# SWDM-21DD8_LV_XX_V1.net
KiCad netlist of a schematic drawn in Altium Designer
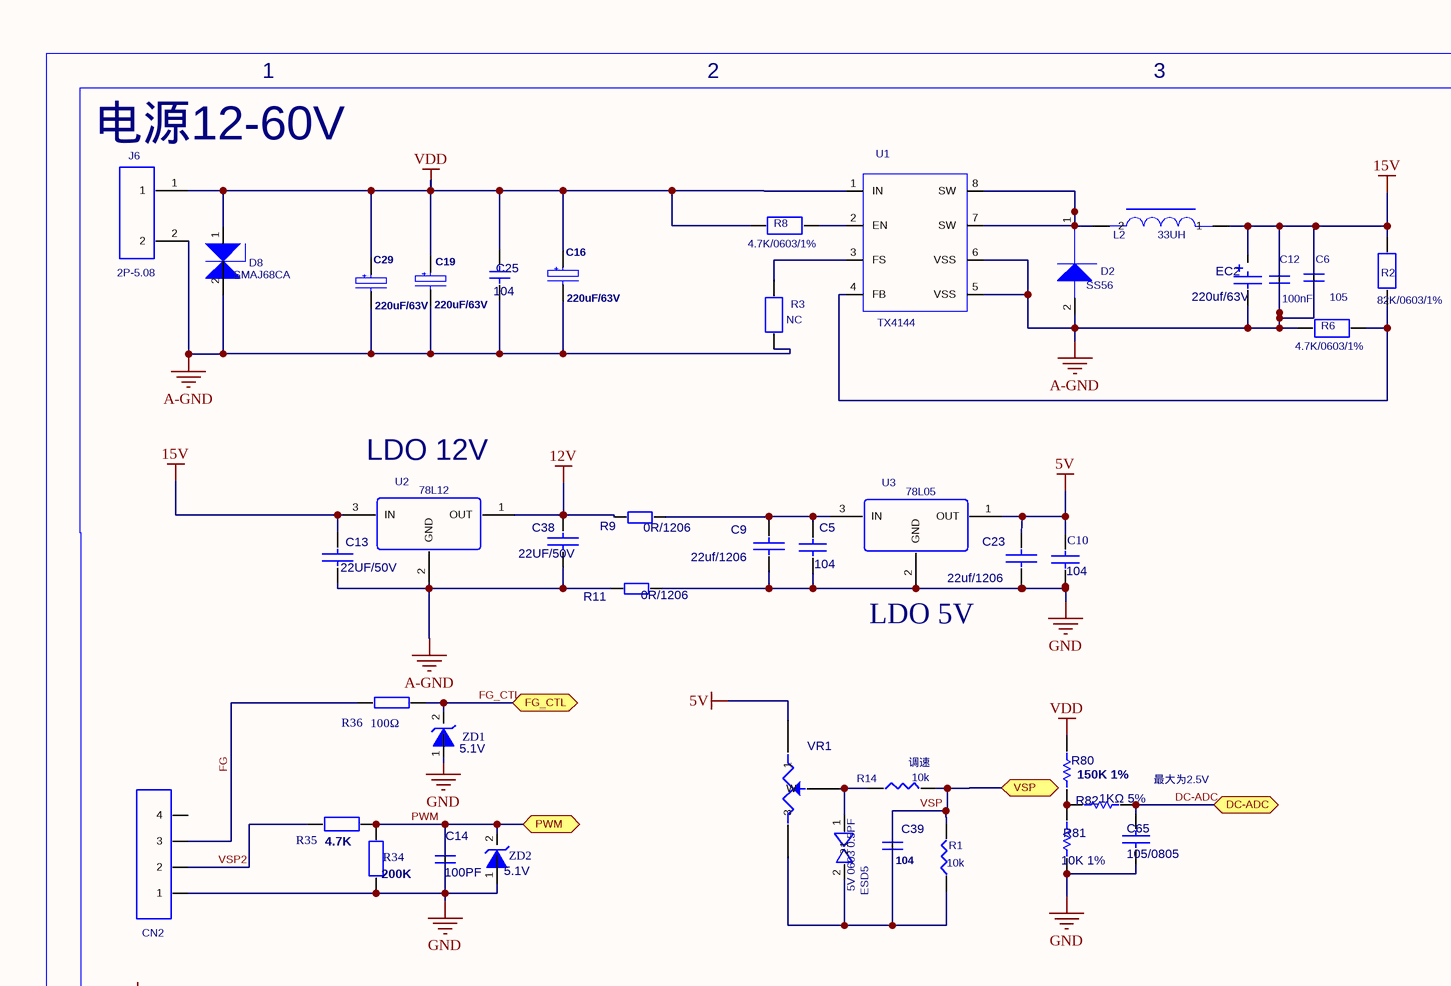
[diagram p0: SWDM-21DD8_LV_XX_V1.SchDoc, top left]
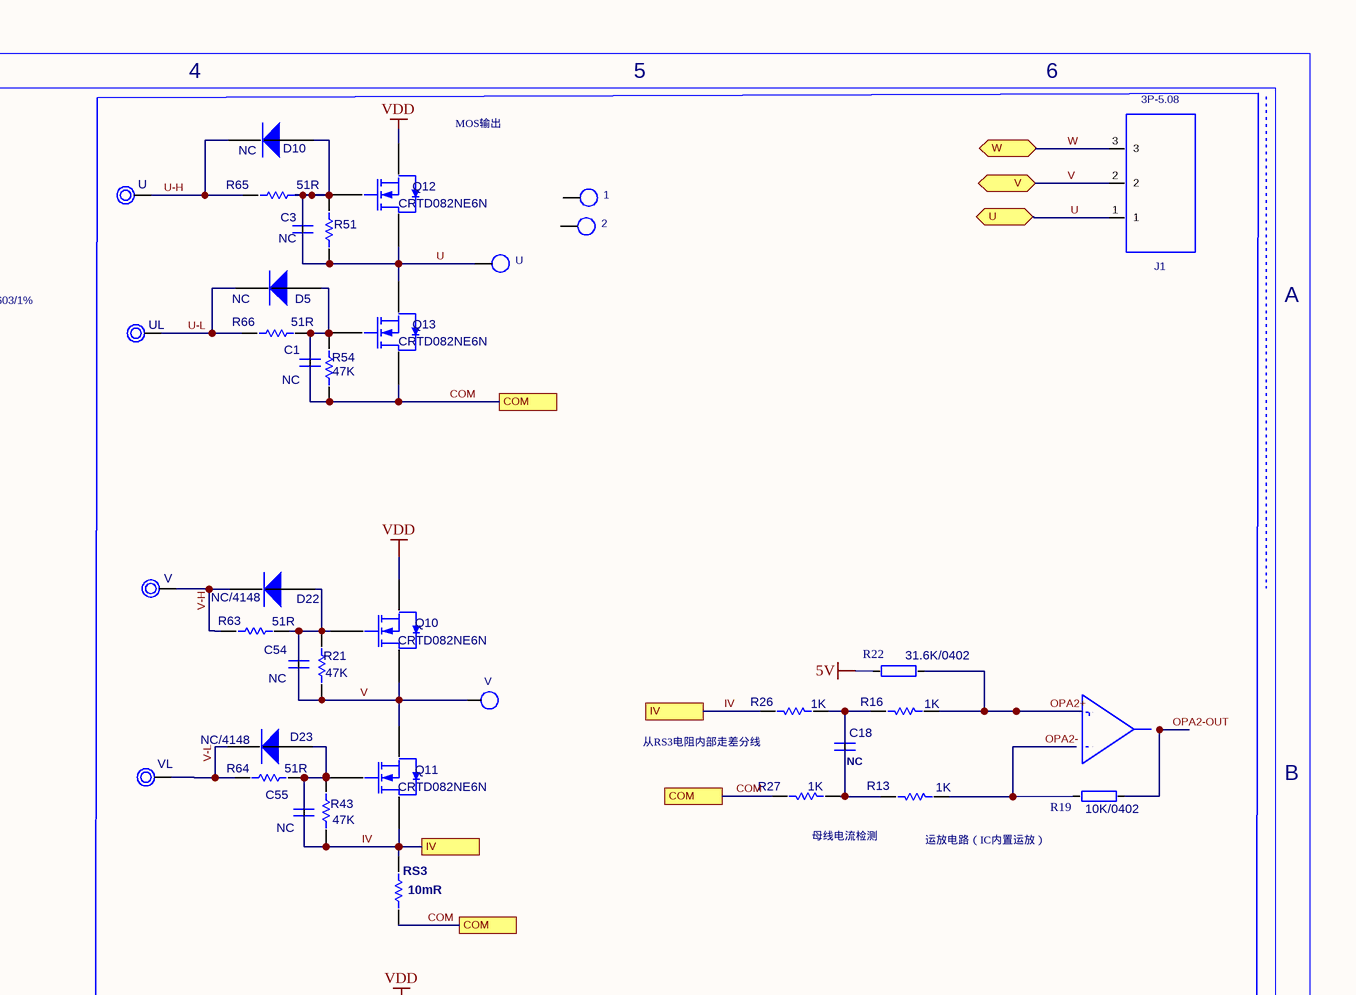
[diagram p1: SWDM-21DD8_LV_XX_V1.SchDoc, top right]
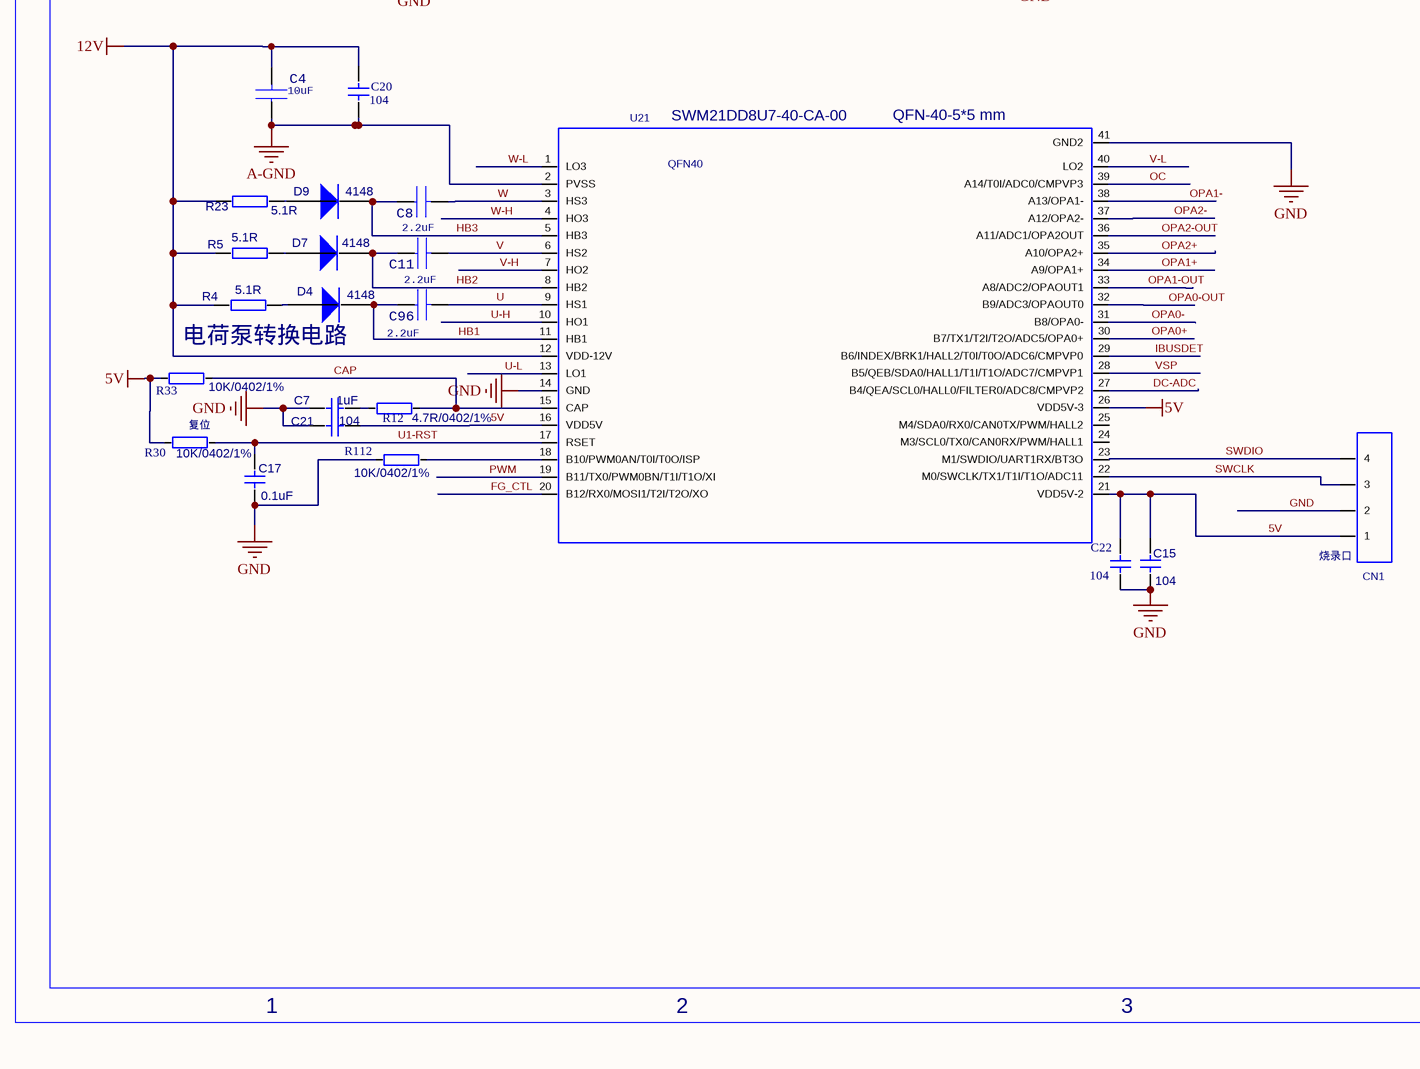
[diagram p2: SWDM-21DD8_LV_XX_V1.SchDoc, bottom left]
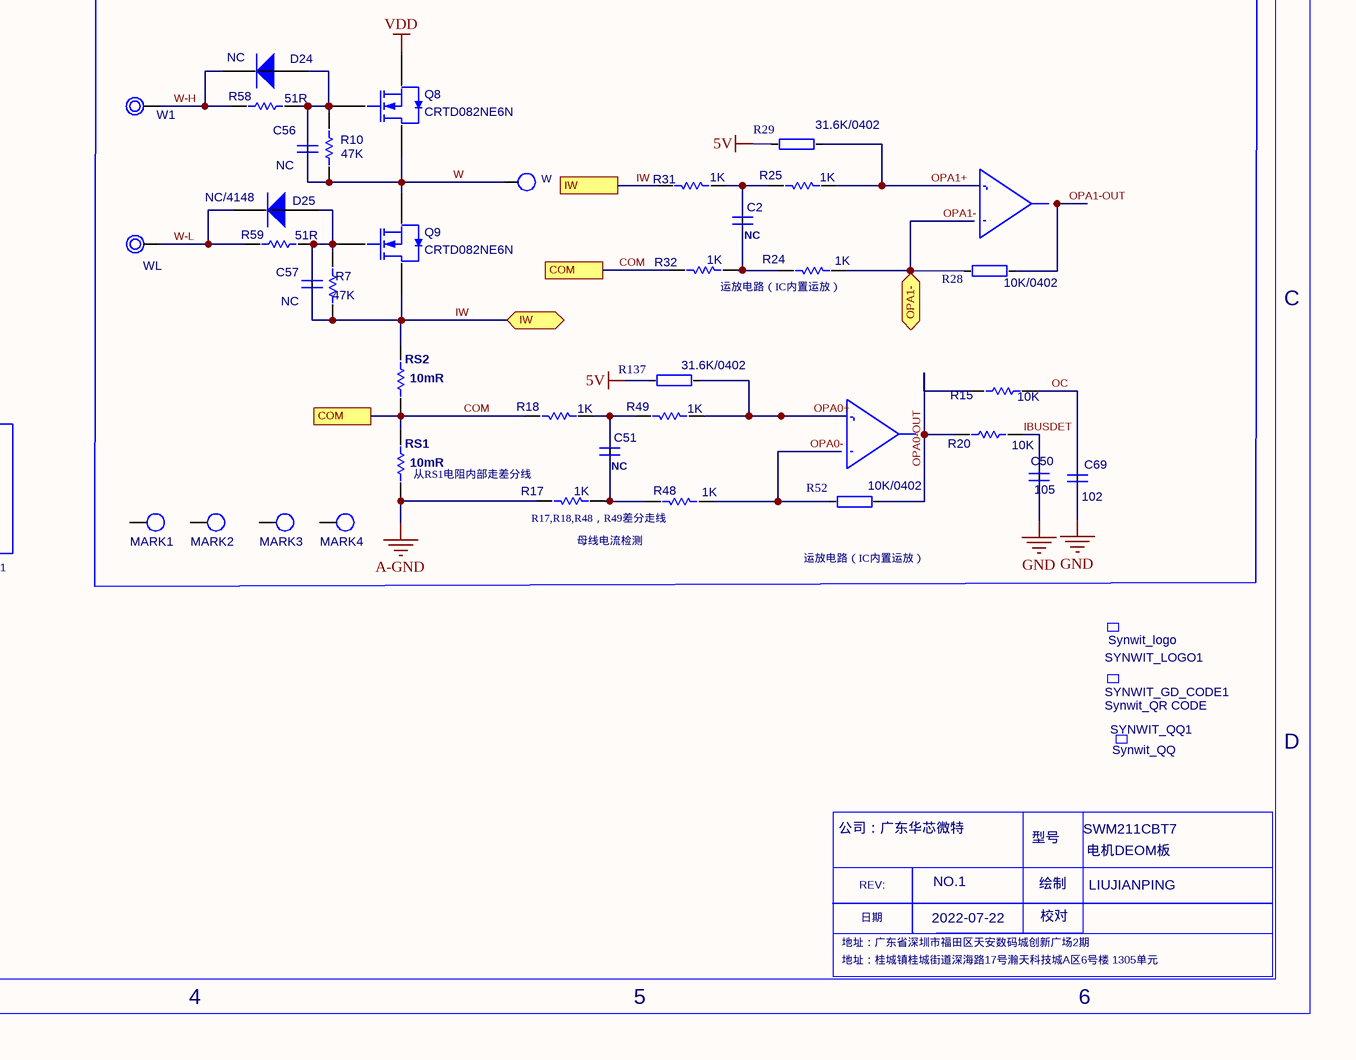
[diagram p3: SWDM-21DD8_LV_XX_V1.SchDoc, bottom right]

(export (version "E")
  (design (tool "Eeschema 10.0.6"))
  (components
    (comp (ref "C1")
      (value "NC")
      (footprint "C0603")
      (description "贴片瓷片电容")
      (libsource (lib "*") (part "C0603"))
    )
    (comp (ref "C2")
      (value "NC")
      (footprint "C0603")
      (fields (field (name "Comment") "C0603"))
      (libsource (lib "*") (part "C0603"))
    )
    (comp (ref "C3")
      (value "NC")
      (footprint "C0603")
      (description "贴片瓷片电容")
      (libsource (lib "*") (part "C0603"))
    )
    (comp (ref "C4")
      (value "10uF")
      (footprint "C0805")
      (description "SMT Resistor 5% UniOhm(厚声)")
      (fields (field (name "Comment") "22uf/25v"))
      (libsource (lib "*") (part "C0805"))
    )
    (comp (ref "C5")
      (value "104")
      (footprint "C0603")
      (description "贴片瓷片电容")
      (libsource (lib "*") (part "CAP_2"))
    )
    (comp (ref "C6")
      (value "105")
      (footprint "C0603")
      (fields (field (name "Comment") "C0603"))
      (libsource (lib "*") (part "C0603"))
    )
    (comp (ref "C7") (value "1uF") (footprint "C0603") (libsource (lib "*") (part "CAP_S")))
    (comp (ref "C8")
      (value "2.2uF")
      (footprint "C0805")
      (fields (field (name "Comment") "C0805"))
      (libsource (lib "*") (part "C0805"))
    )
    (comp (ref "C9")
      (value "22uf/1206")
      (footprint "C1206")
      (description "Capacitor")
      (libsource (lib "*") (part "C1206"))
    )
    (comp (ref "C10")
      (value "104")
      (footprint "C0603")
      (description "贴片瓷片电容")
      (libsource (lib "*") (part "CAP_2"))
    )
    (comp (ref "C11")
      (value "2.2uF")
      (footprint "C0805")
      (fields (field (name "Comment") "C0805"))
      (libsource (lib "*") (part "C0805"))
    )
    (comp (ref "C12")
      (value "100nF")
      (footprint "C0603")
      (fields (field (name "Comment") "C0603"))
      (libsource (lib "*") (part "C0603"))
    )
    (comp (ref "C13")
      (value "22UF/50V")
      (footprint "C1206")
      (description "电解电容")
      (libsource (lib "*") (part "C1206"))
    )
    (comp (ref "C14")
      (value "100PF")
      (footprint "C0603")
      (description "Capacitor")
      (libsource (lib "*") (part "C0603"))
    )
    (comp (ref "C15") (value "104") (footprint "C0603") (libsource (lib "*") (part "CAP_S")))
    (comp (ref "C16")
      (value "220uF/63V")
      (footprint "CAP_10X12")
      (fields
        (field (name "VOLTAGE") "16V")
        (field (name "TOLERANCE") "20%")
        (field (name "Comment") "CAP_10X12")
      )
      (libsource (lib "*") (part "CAP_10X12"))
    )
    (comp (ref "C17") (value "0.1uF") (footprint "C0603") (libsource (lib "*") (part "CAP_S")))
    (comp (ref "C18")
      (value "NC")
      (footprint "C0603")
      (fields (field (name "Comment") "C0603"))
      (libsource (lib "*") (part "C0603"))
    )
    (comp (ref "C19")
      (value "220uF/63V")
      (footprint "CAP_10X12")
      (fields
        (field (name "VOLTAGE") "16V")
        (field (name "TOLERANCE") "20%")
        (field (name "Comment") "CAP_10X12")
      )
      (libsource (lib "*") (part "CAP_10X12"))
    )
    (comp (ref "C20") (value "104") (footprint "C0603") (libsource (lib "*") (part "CAP_S")))
    (comp (ref "C21") (value "104") (footprint "C0603") (libsource (lib "*") (part "CAP_S")))
    (comp (ref "C22") (value "104") (footprint "C0603") (libsource (lib "*") (part "CAP_S")))
    (comp (ref "C23")
      (value "22uf/1206")
      (footprint "C1206")
      (description "Capacitor")
      (libsource (lib "*") (part "C1206"))
    )
    (comp (ref "C25") (value "104") (footprint "C0603") (libsource (lib "*") (part "CAP_S")))
    (comp (ref "C29")
      (value "220uF/63V")
      (footprint "CAP_10X12")
      (fields
        (field (name "VOLTAGE") "16V")
        (field (name "TOLERANCE") "20%")
        (field (name "Comment") "CAP_10X12")
      )
      (libsource (lib "*") (part "CAP_10X12"))
    )
    (comp (ref "C38")
      (value "22UF/50V")
      (footprint "C1206")
      (description "电解电容")
      (libsource (lib "*") (part "C1206"))
    )
    (comp (ref "C39")
      (value "104")
      (footprint "C0603")
      (fields (field (name "Comment") "C0603"))
      (libsource (lib "") (part "C0603_1"))
    )
    (comp (ref "C50")
      (value "105")
      (footprint "C0603")
      (description "贴片瓷片电容")
      (libsource (lib "*") (part "C0603"))
    )
    (comp (ref "C51")
      (value "NC")
      (footprint "C0603")
      (fields (field (name "Comment") "C0603"))
      (libsource (lib "*") (part "C0603"))
    )
    (comp (ref "C54")
      (value "NC")
      (footprint "C0603")
      (description "贴片瓷片电容")
      (libsource (lib "*") (part "C0603"))
    )
    (comp (ref "C55")
      (value "NC")
      (footprint "C0603")
      (description "贴片瓷片电容")
      (libsource (lib "*") (part "C0603"))
    )
    (comp (ref "C56")
      (value "NC")
      (footprint "C0603")
      (description "贴片瓷片电容")
      (libsource (lib "") (part "C0603_1"))
    )
    (comp (ref "C57")
      (value "NC")
      (footprint "C0603")
      (description "贴片瓷片电容")
      (libsource (lib "*") (part "C0603"))
    )
    (comp (ref "C65")
      (value "105/0805")
      (footprint "C0603")
      (description "Capacitor")
      (libsource (lib "*") (part "CAP"))
    )
    (comp (ref "C69")
      (value "102")
      (footprint "C0603")
      (description "贴片瓷片电容")
      (libsource (lib "") (part "C0603_1"))
    )
    (comp (ref "C96")
      (value "2.2uF")
      (footprint "C0805")
      (fields (field (name "Comment") "C0805"))
      (libsource (lib "*") (part "C0805"))
    )
    (comp (ref "CN1")
      (value "SWD1")
      (footprint "4P-2.54-8")
      (description "接插件  DS-5.1CN4  DS-2.54CWB-4")
      (libsource (lib "*") (part "4P-2.54-8"))
    )
    (comp (ref "CN2")
      (value "SWD1")
      (footprint "4P-2.54-8")
      (description "接插件  DS-5.1CN4  DS-2.54CWB-4")
      (libsource (lib "*") (part "4P-2.54-8"))
    )
    (comp (ref "D2")
      (value "SS56")
      (footprint "SMA")
      (fields (field (name "PART_NUMBER") "DIO-4148-01") (field (name "Comment") "DIODE_2"))
      (libsource (lib "*") (part "DIODE_2"))
    )
    (comp (ref "D4")
      (value "4148")
      (footprint "SOD-123/3")
      (description "Default Diode")
      (libsource (lib "*") (part "DIODE"))
    )
    (comp (ref "D5")
      (value "NC")
      (footprint "SOD-323")
      (description "Default Diode")
      (libsource (lib "*") (part "DIODE"))
    )
    (comp (ref "D7")
      (value "4148")
      (footprint "SOD-123/3")
      (description "Default Diode")
      (libsource (lib "*") (part "DIODE"))
    )
    (comp (ref "D8")
      (value "SMAJ68CA")
      (footprint "Y_SMA-TVS")
      (fields (field (name "PART_NUMBER") "DIO-4148-01") (field (name "Comment") "DIODE_4"))
      (libsource (lib "*") (part "DIODE_4"))
    )
    (comp (ref "D9")
      (value "4148")
      (footprint "SOD-123/3")
      (description "Default Diode")
      (libsource (lib "*") (part "DIODE"))
    )
    (comp (ref "D10")
      (value "NC")
      (footprint "SOD-323")
      (description "Default Diode")
      (libsource (lib "*") (part "DIODE"))
    )
    (comp (ref "D22")
      (value "NC/4148")
      (footprint "SOD-323")
      (description "Default Diode")
      (libsource (lib "*") (part "DIODE"))
    )
    (comp (ref "D23")
      (value "NC/4148")
      (footprint "SOD-323")
      (description "Default Diode")
      (libsource (lib "*") (part "DIODE"))
    )
    (comp (ref "D24")
      (value "NC")
      (footprint "SOD-323")
      (description "Default Diode")
      (libsource (lib "*") (part "DIODE"))
    )
    (comp (ref "D25")
      (value "NC/4148")
      (footprint "SOD-323")
      (description "Default Diode")
      (libsource (lib "*") (part "DIODE"))
    )
    (comp (ref "EC2")
      (value "220uf/63V")
      (footprint "C-DD6X9")
      (description "Polarized Capacitor (Axial)")
      (libsource (lib "*") (part "CAP_POL2"))
    )
    (comp (ref "ESD5")
      (value "5V 0603 0.5PF")
      (footprint "ESD0603")
      (fields (field (name "Comment") "ESD0603"))
      (libsource (lib "*") (part "ESD0603"))
    )
    (comp (ref "J1") (value "3P-5.08") (footprint "3P-5.08") (libsource (lib "*") (part "3P-5.08")))
    (comp (ref "J6") (value "2P-5.08") (footprint "2P-5.08") (libsource (lib "*") (part "2P-5.08")))
    (comp (ref "L2")
      (value "33UH")
      (footprint "L-8050")
      (fields (field (name "Comment") "L-8050"))
      (libsource (lib "*") (part "L-8050"))
    )
    (comp (ref "MARK1") (value "TEST POINT") (footprint "TP60") (libsource (lib "*") (part "TEST_POINT")))
    (comp (ref "MARK2") (value "TEST POINT") (footprint "TP60") (libsource (lib "*") (part "TEST_POINT")))
    (comp (ref "MARK3") (value "TEST POINT") (footprint "TP60") (libsource (lib "*") (part "TEST_POINT")))
    (comp (ref "MARK4") (value "TEST POINT") (footprint "TP60") (libsource (lib "*") (part "TEST_POINT")))
    (comp (ref "Q8")
      (value "CRTD082NE6N")
      (footprint "TO-252-2-180")
      (description "MOS(场效应管)")
      (libsource (lib "*") (part "AO3400A_NZKDZ_X0YV1T_SOT-23"))
    )
    (comp (ref "Q9")
      (value "CRTD082NE6N")
      (footprint "TO-252-2-180")
      (description "MOS(场效应管)")
      (libsource (lib "*") (part "AO3400A_NZKDZ_X0YV1T_SOT-23"))
    )
    (comp (ref "Q10")
      (value "CRTD082NE6N")
      (footprint "TO-252-2-180")
      (description "MOS(场效应管)")
      (libsource (lib "*") (part "AO3400A_NZKDZ_X0YV1T_SOT-23"))
    )
    (comp (ref "Q11")
      (value "CRTD082NE6N")
      (footprint "TO-252-2-180")
      (description "MOS(场效应管)")
      (libsource (lib "*") (part "AO3400A_NZKDZ_X0YV1T_SOT-23"))
    )
    (comp (ref "Q12")
      (value "CRTD082NE6N")
      (footprint "TO-252-2-180")
      (description "MOS(场效应管)")
      (libsource (lib "*") (part "AO3400A_NZKDZ_X0YV1T_SOT-23"))
    )
    (comp (ref "Q13")
      (value "CRTD082NE6N")
      (footprint "TO-252-2-180")
      (description "MOS(场效应管)")
      (libsource (lib "*") (part "AO3400A_NZKDZ_X0YV1T_SOT-23"))
    )
    (comp (ref "R1")
      (value "10K")
      (footprint "R0603")
      (fields (field (name "COMMENT_1") "10k"))
      (libsource (lib "") (part "10K_2_1"))
    )
    (comp (ref "R2") (value "82K/0603/1%") (footprint "R0603") (libsource (lib "*") (part "R0603")))
    (comp (ref "R3") (value "NC") (footprint "R0603") (libsource (lib "*") (part "R0603")))
    (comp (ref "R4") (value "5.1R") (footprint "R1206") (libsource (lib "*") (part "RES_T")))
    (comp (ref "R5") (value "5.1R") (footprint "R1206") (libsource (lib "*") (part "RES_T")))
    (comp (ref "R6") (value "4.7K/0603/1%") (footprint "R0603") (libsource (lib "*") (part "R0603")))
    (comp (ref "R7")
      (value "47K")
      (footprint "R0603")
      (description "Semiconductor Resistor")
      (libsource (lib "*") (part "RES_SEMI"))
    )
    (comp (ref "R8") (value "4.7K/0603/1%") (footprint "R0603") (libsource (lib "*") (part "R0603")))
    (comp (ref "R9")
      (value "0R/1206")
      (footprint "1206R")
      (description "贴片 电阻器")
      (libsource (lib "") (part "R1206_1"))
    )
    (comp (ref "R10")
      (value "47K")
      (footprint "R0603")
      (description "Semiconductor Resistor")
      (libsource (lib "*") (part "RES_SEMI"))
    )
    (comp (ref "R11")
      (value "0R/1206")
      (footprint "1206R")
      (description "贴片 电阻器")
      (libsource (lib "*") (part "R1206"))
    )
    (comp (ref "R12")
      (value "4.7R/0402/1%")
      (footprint "R0603")
      (description "贴片电阻")
      (libsource (lib "*") (part "R0402"))
    )
    (comp (ref "R13")
      (value "1K")
      (footprint "R0603")
      (description "Semiconductor Resistor")
      (libsource (lib "*") (part "RES_SEMI"))
    )
    (comp (ref "R14")
      (value "10K")
      (footprint "R0603")
      (fields (field (name "COMMENT_1") "10k"))
      (libsource (lib "*") (part "10K_2"))
    )
    (comp (ref "R15")
      (value "10K")
      (footprint "R0603")
      (description "Semiconductor Resistor")
      (libsource (lib "*") (part "RES_SEMI"))
    )
    (comp (ref "R16")
      (value "1K")
      (footprint "R0603")
      (description "Semiconductor Resistor")
      (libsource (lib "*") (part "RES_SEMI"))
    )
    (comp (ref "R17")
      (value "1K")
      (footprint "R0603")
      (description "Semiconductor Resistor")
      (libsource (lib "*") (part "RES_SEMI"))
    )
    (comp (ref "R18")
      (value "1K")
      (footprint "R0603")
      (description "Semiconductor Resistor")
      (libsource (lib "*") (part "RES_SEMI"))
    )
    (comp (ref "R19")
      (value "10K/0402")
      (footprint "R0603")
      (description "贴片电阻")
      (libsource (lib "*") (part "R0402"))
    )
    (comp (ref "R20")
      (value "10K")
      (footprint "R0603")
      (description "Semiconductor Resistor")
      (libsource (lib "*") (part "RES_SEMI"))
    )
    (comp (ref "R21")
      (value "47K")
      (footprint "R0603")
      (description "Semiconductor Resistor")
      (libsource (lib "*") (part "RES_SEMI"))
    )
    (comp (ref "R22")
      (value "31.6K/0402")
      (footprint "R0603")
      (description "贴片电阻")
      (libsource (lib "*") (part "R0402"))
    )
    (comp (ref "R23") (value "5.1R") (footprint "R1206") (libsource (lib "*") (part "RES_T")))
    (comp (ref "R24")
      (value "1K")
      (footprint "R0603")
      (description "Semiconductor Resistor")
      (libsource (lib "*") (part "RES_SEMI"))
    )
    (comp (ref "R25")
      (value "1K")
      (footprint "R0603")
      (description "Semiconductor Resistor")
      (libsource (lib "*") (part "RES_SEMI"))
    )
    (comp (ref "R26")
      (value "1K")
      (footprint "R0603")
      (description "Semiconductor Resistor")
      (libsource (lib "*") (part "RES_SEMI"))
    )
    (comp (ref "R27")
      (value "1K")
      (footprint "R0603")
      (description "Semiconductor Resistor")
      (libsource (lib "*") (part "RES_SEMI"))
    )
    (comp (ref "R28")
      (value "10K/0402")
      (footprint "R0603")
      (description "贴片电阻")
      (libsource (lib "*") (part "R0402"))
    )
    (comp (ref "R29")
      (value "31.6K/0402")
      (footprint "R0603")
      (description "贴片电阻")
      (libsource (lib "*") (part "R0402"))
    )
    (comp (ref "R30")
      (value "10K/0402/1%")
      (footprint "R0603")
      (description "贴片电阻")
      (libsource (lib "*") (part "R0402"))
    )
    (comp (ref "R31")
      (value "1K")
      (footprint "R0603")
      (description "Semiconductor Resistor")
      (libsource (lib "*") (part "RES_SEMI"))
    )
    (comp (ref "R32")
      (value "1K")
      (footprint "R0603")
      (description "Semiconductor Resistor")
      (libsource (lib "*") (part "RES_SEMI"))
    )
    (comp (ref "R33")
      (value "10K/0402/1%")
      (footprint "R0603")
      (description "贴片电阻")
      (libsource (lib "*") (part "R0402"))
    )
    (comp (ref "R34")
      (value "200K")
      (footprint "R0603")
      (description "电阻, Resistor")
      (fields (field (name "COMMEN") "200K"))
      (libsource (lib "*") (part "RES"))
    )
    (comp (ref "R35")
      (value "4.7K")
      (footprint "R0603A")
      (description "贴片电阻")
      (libsource (lib "*") (part "0603_1KKC_(1001)_1%"))
    )
    (comp (ref "R36") (value "100Ω") (footprint "R0603") (libsource (lib "*") (part "RES2")))
    (comp (ref "R43")
      (value "47K")
      (footprint "R0603")
      (description "Semiconductor Resistor")
      (libsource (lib "*") (part "RES_SEMI"))
    )
    (comp (ref "R48")
      (value "1K")
      (footprint "R0603")
      (description "Semiconductor Resistor")
      (libsource (lib "*") (part "RES_SEMI"))
    )
    (comp (ref "R49")
      (value "1K")
      (footprint "R0603")
      (description "Semiconductor Resistor")
      (libsource (lib "*") (part "RES_SEMI"))
    )
    (comp (ref "R51")
      (value "47K")
      (footprint "R0603")
      (description "Semiconductor Resistor")
      (libsource (lib "*") (part "RES_SEMI"))
    )
    (comp (ref "R52")
      (value "10K/0402")
      (footprint "R0603")
      (description "贴片电阻")
      (libsource (lib "*") (part "R0402"))
    )
    (comp (ref "R54")
      (value "47K")
      (footprint "R0603")
      (description "Semiconductor Resistor")
      (libsource (lib "*") (part "RES_SEMI"))
    )
    (comp (ref "R58")
      (value "51R")
      (footprint "R0603")
      (description "Semiconductor Resistor")
      (libsource (lib "*") (part "RES_SEMI"))
    )
    (comp (ref "R59")
      (value "51R")
      (footprint "R0603")
      (description "Semiconductor Resistor")
      (libsource (lib "*") (part "RES_SEMI"))
    )
    (comp (ref "R63")
      (value "51R")
      (footprint "R0603")
      (description "Semiconductor Resistor")
      (libsource (lib "*") (part "RES_SEMI"))
    )
    (comp (ref "R64")
      (value "51R")
      (footprint "R0603")
      (description "Semiconductor Resistor")
      (libsource (lib "*") (part "RES_SEMI"))
    )
    (comp (ref "R65")
      (value "51R")
      (footprint "R0603")
      (description "Semiconductor Resistor")
      (libsource (lib "*") (part "RES_SEMI"))
    )
    (comp (ref "R66")
      (value "51R")
      (footprint "R0603")
      (description "Semiconductor Resistor")
      (libsource (lib "*") (part "RES_SEMI"))
    )
    (comp (ref "R80")
      (value "150K 1%")
      (footprint "R0603")
      (description "Semiconductor Resistor")
      (libsource (lib "*") (part "RES_SEMI"))
    )
    (comp (ref "R81")
      (value "10K 1%")
      (footprint "R0603")
      (description "Semiconductor Resistor")
      (libsource (lib "*") (part "RES_SEMI"))
    )
    (comp (ref "R82")
      (value "1KΩ 5%")
      (footprint "R0603")
      (description "Semiconductor Resistor")
      (libsource (lib "*") (part "RES_SEMI"))
    )
    (comp (ref "R112")
      (value "10K/0402/1%")
      (footprint "R0603")
      (description "贴片电阻")
      (libsource (lib "*") (part "R0402"))
    )
    (comp (ref "R137")
      (value "31.6K/0402")
      (footprint "R0603")
      (description "贴片电阻")
      (libsource (lib "*") (part "R0402"))
    )
    (comp (ref "RS1")
      (value "10mR")
      (footprint "2512R_6332")
      (description "Semiconductor Resistor")
      (libsource (lib "*") (part "RES_2512"))
    )
    (comp (ref "RS2")
      (value "10mR")
      (footprint "2512R_6332")
      (description "Semiconductor Resistor")
      (libsource (lib "*") (part "RES_2512"))
    )
    (comp (ref "RS3")
      (value "10mR")
      (footprint "2512R_6332")
      (description "Semiconductor Resistor")
      (libsource (lib "*") (part "RES_2512"))
    )
    (comp (ref "SYNWIT_GD_CODE1")
      (value "Synwit_QR CODE")
      (footprint "SYNWIT_GD_QR_CODE")
      (libsource (lib "*") (part "SYNWIT_LOGO"))
    )
    (comp (ref "SYNWIT_LOGO1")
      (value "Synwit_logo")
      (footprint "SYNWIT_LOGO_14X7")
      (libsource (lib "*") (part "SYNWIT_LOGO"))
    )
    (comp (ref "SYNWIT_QQ1")
      (value "Synwit_QQ")
      (footprint "SYNWIT_QQ")
      (libsource (lib "*") (part "SYNWIT_LOGO"))
    )
    (comp (ref "T1")
      (value "U")
      (footprint "TEST")
      (fields (field (name "Comment") "TEST"))
      (libsource (lib "*") (part "TEST"))
    )
    (comp (ref "T2")
      (value "1")
      (footprint "TEST")
      (fields (field (name "Comment") "TEST"))
      (libsource (lib "*") (part "TEST"))
    )
    (comp (ref "T3")
      (value "V")
      (footprint "TEST")
      (fields (field (name "Comment") "TEST"))
      (libsource (lib "*") (part "TEST"))
    )
    (comp (ref "T4")
      (value "W")
      (footprint "TEST")
      (fields (field (name "Comment") "TEST"))
      (libsource (lib "*") (part "TEST"))
    )
    (comp (ref "T6")
      (value "2")
      (footprint "TEST")
      (fields (field (name "Comment") "TEST"))
      (libsource (lib "*") (part "TEST"))
    )
    (comp (ref "U") (value "TP_1") (footprint "TP60") (libsource (lib "*") (part "TP_1")))
    (comp (ref "U1") (value "TX4144") (footprint "SOP8") (libsource (lib "*") (part "TX4144")))
    (comp (ref "U2")
      (value "78L12")
      (footprint "78L05")
      (fields (field (name "BOM_MANUFACTURER_PART") "78L05") (field (name "BOM_SUPPLIER_PART") "C112446"))
      (libsource (lib "*") (part "78L05"))
    )
    (comp (ref "U3")
      (value "78L05")
      (footprint "78L05")
      (fields (field (name "BOM_SUPPLIER_PART") "C112446"))
      (libsource (lib "*") (part "78L05"))
    )
    (comp (ref "U21") (value "QFN40") (footprint "QFN40") (libsource (lib "*") (part "QFN40")))
    (comp (ref "UL") (value "TP_1") (footprint "TP60") (libsource (lib "*") (part "TP_1")))
    (comp (ref "V") (value "TP_1") (footprint "TP60") (libsource (lib "*") (part "TP_1")))
    (comp (ref "VL") (value "TP_1") (footprint "TP60") (libsource (lib "*") (part "TP_1")))
    (comp (ref "VR1")
      (value "~")
      (footprint "VR6")
      (description "Potentiometer")
      (libsource (lib "*") (part "RV-3296"))
    )
    (comp (ref "W1") (value "TP_1") (footprint "TP60") (libsource (lib "*") (part "TP_1")))
    (comp (ref "WL") (value "TP_1") (footprint "TP60") (libsource (lib "*") (part "TP_1")))
    (comp (ref "ZD1") (value "5.1V") (footprint "SOD-123") (libsource (lib "*") (part "DIODE_W")))
    (comp (ref "ZD2") (value "5.1V") (footprint "SOD-123") (libsource (lib "*") (part "DIODE_W")))
  )
  (nets
    (net (code "1") (name "/CAP") (class "Default")
      (node (ref "R12") (pin "2") (pinfunction "2_2") (pintype "passive"))
      (node (ref "R33") (pin "2") (pinfunction "2_2") (pintype "passive"))
      (node (ref "U21") (pin "15") (pinfunction "CAP_15") (pintype "passive"))
    )
    (net (code "2") (name "/COM") (class "Default")
      (node (ref "C1") (pin "1") (pinfunction "1_1") (pintype "passive"))
      (node (ref "Q13") (pin "3") (pinfunction "D_3") (pintype "passive"))
      (node (ref "R18") (pin "1") (pinfunction "1_1") (pintype "passive"))
      (node (ref "R27") (pin "1") (pinfunction "1_1") (pintype "passive"))
      (node (ref "R32") (pin "1") (pinfunction "1_1") (pintype "passive"))
      (node (ref "R54") (pin "1") (pinfunction "1_1") (pintype "passive"))
      (node (ref "RS1") (pin "2") (pinfunction "2_2") (pintype "passive"))
      (node (ref "RS2") (pin "1") (pinfunction "1_1") (pintype "passive"))
      (node (ref "RS3") (pin "1") (pinfunction "1_1") (pintype "passive"))
    )
    (net (code "3") (name "/DC-ADC") (class "Default")
      (node (ref "C65") (pin "1") (pinfunction "1_1") (pintype "passive"))
      (node (ref "R82") (pin "1") (pinfunction "1_1") (pintype "passive"))
      (node (ref "U21") (pin "27") (pinfunction "B4/QEA/SCL0/HALL0/FILTER0/ADC8/CMPVP2_27") (pintype "passive"))
    )
    (net (code "4") (name "/FG") (class "Default")
      (node (ref "CN2") (pin "3") (pinfunction "3_3") (pintype "passive"))
      (node (ref "R36") (pin "2") (pinfunction "2_2") (pintype "passive"))
    )
    (net (code "5") (name "/FG_CTL") (class "Default")
      (node (ref "R36") (pin "1") (pinfunction "1_1") (pintype "passive"))
      (node (ref "U21") (pin "20") (pinfunction "B12/RX0/MOSI1/T2I/T2O/XO_20") (pintype "passive"))
      (node (ref "ZD1") (pin "2") (pinfunction "2_2") (pintype "passive"))
    )
    (net (code "6") (name "/HB1") (class "Default")
      (node (ref "C96") (pin "1") (pinfunction "1_1") (pintype "passive"))
      (node (ref "D4") (pin "2") (pinfunction "K_2") (pintype "passive"))
      (node (ref "U21") (pin "11") (pinfunction "HB1_11") (pintype "passive"))
    )
    (net (code "7") (name "/HB2") (class "Default")
      (node (ref "C11") (pin "1") (pinfunction "1_1") (pintype "passive"))
      (node (ref "D7") (pin "2") (pinfunction "K_2") (pintype "passive"))
      (node (ref "U21") (pin "8") (pinfunction "HB2_8") (pintype "passive"))
    )
    (net (code "8") (name "/HB3") (class "Default")
      (node (ref "C8") (pin "1") (pinfunction "1_1") (pintype "passive"))
      (node (ref "D9") (pin "2") (pinfunction "K_2") (pintype "passive"))
      (node (ref "U21") (pin "5") (pinfunction "HB3_5") (pintype "passive"))
    )
    (net (code "9") (name "/IBUSDET") (class "Default")
      (node (ref "C50") (pin "2") (pinfunction "2_2") (pintype "passive"))
      (node (ref "R20") (pin "2") (pinfunction "2_2") (pintype "passive"))
      (node (ref "U21") (pin "29") (pinfunction "B6/INDEX/BRK1/HALL2/T0I/T0O/ADC6/CMPVP0_29") (pintype "passive"))
    )
    (net (code "10") (name "/IV") (class "Default")
      (node (ref "C55") (pin "1") (pinfunction "1_1") (pintype "passive"))
      (node (ref "Q11") (pin "3") (pinfunction "D_3") (pintype "passive"))
      (node (ref "R26") (pin "1") (pinfunction "1_1") (pintype "passive"))
      (node (ref "R43") (pin "1") (pinfunction "1_1") (pintype "passive"))
      (node (ref "RS3") (pin "2") (pinfunction "2_2") (pintype "passive"))
    )
    (net (code "11") (name "/IW") (class "Default")
      (node (ref "C57") (pin "1") (pinfunction "1_1") (pintype "passive"))
      (node (ref "Q9") (pin "3") (pinfunction "D_3") (pintype "passive"))
      (node (ref "R31") (pin "1") (pinfunction "1_1") (pintype "passive"))
      (node (ref "R7") (pin "1") (pinfunction "1_1") (pintype "passive"))
      (node (ref "RS2") (pin "2") (pinfunction "2_2") (pintype "passive"))
    )
    (net (code "12") (name "/OC") (class "Default")
      (node (ref "C69") (pin "2") (pinfunction "2_2") (pintype "passive"))
      (node (ref "R15") (pin "2") (pinfunction "2_2") (pintype "passive"))
      (node (ref "U21") (pin "39") (pinfunction "A14/T0I/ADC0/CMPVP3_39") (pintype "passive"))
    )
    (net (code "13") (name "/OPA0+") (class "Default")
      (node (ref "R137") (pin "1") (pinfunction "1_1") (pintype "passive"))
      (node (ref "R49") (pin "2") (pinfunction "2_2") (pintype "passive"))
      (node (ref "U21") (pin "30") (pinfunction "B7/TX1/T2I/T2O/ADC5/OPA0+_30") (pintype "passive"))
    )
    (net (code "14") (name "/OPA0-") (class "Default")
      (node (ref "R48") (pin "2") (pinfunction "2_2") (pintype "passive"))
      (node (ref "R52") (pin "2") (pinfunction "2_2") (pintype "passive"))
      (node (ref "U21") (pin "31") (pinfunction "B8/OPA0-_31") (pintype "passive"))
    )
    (net (code "15") (name "/OPA0-OUT") (class "Default")
      (node (ref "R15") (pin "1") (pinfunction "1_1") (pintype "passive"))
      (node (ref "R20") (pin "1") (pinfunction "1_1") (pintype "passive"))
      (node (ref "R52") (pin "1") (pinfunction "1_1") (pintype "passive"))
      (node (ref "U21") (pin "32") (pinfunction "B9/ADC3/OPAOUT0_32") (pintype "passive"))
    )
    (net (code "16") (name "/OPA1+") (class "Default")
      (node (ref "R25") (pin "2") (pinfunction "2_2") (pintype "passive"))
      (node (ref "R29") (pin "1") (pinfunction "1_1") (pintype "passive"))
      (node (ref "U21") (pin "34") (pinfunction "A9/OPA1+_34") (pintype "passive"))
    )
    (net (code "17") (name "/OPA1-") (class "Default")
      (node (ref "R24") (pin "2") (pinfunction "2_2") (pintype "passive"))
      (node (ref "R28") (pin "2") (pinfunction "2_2") (pintype "passive"))
      (node (ref "U21") (pin "38") (pinfunction "A13/OPA1-_38") (pintype "passive"))
    )
    (net (code "18") (name "/OPA1-OUT") (class "Default")
      (node (ref "R28") (pin "1") (pinfunction "1_1") (pintype "passive"))
      (node (ref "U21") (pin "33") (pinfunction "A8/ADC2/OPAOUT1_33") (pintype "passive"))
    )
    (net (code "19") (name "/OPA2+") (class "Default")
      (node (ref "R16") (pin "2") (pinfunction "2_2") (pintype "passive"))
      (node (ref "R22") (pin "1") (pinfunction "1_1") (pintype "passive"))
      (node (ref "U21") (pin "35") (pinfunction "A10/OPA2+_35") (pintype "passive"))
    )
    (net (code "20") (name "/OPA2-") (class "Default")
      (node (ref "R13") (pin "2") (pinfunction "2_2") (pintype "passive"))
      (node (ref "R19") (pin "2") (pinfunction "2_2") (pintype "passive"))
      (node (ref "U21") (pin "37") (pinfunction "A12/OPA2-_37") (pintype "passive"))
    )
    (net (code "21") (name "/OPA2-OUT") (class "Default")
      (node (ref "R19") (pin "1") (pinfunction "1_1") (pintype "passive"))
      (node (ref "U21") (pin "36") (pinfunction "A11/ADC1/OPA2OUT_36") (pintype "passive"))
    )
    (net (code "22") (name "/PWM") (class "Default")
      (node (ref "C14") (pin "1") (pinfunction "1_1") (pintype "passive"))
      (node (ref "R34") (pin "1") (pinfunction "1_1") (pintype "passive"))
      (node (ref "R35") (pin "2") (pinfunction "2_2") (pintype "passive"))
      (node (ref "U21") (pin "19") (pinfunction "B11/TX0/PWM0BN/T1I/T1O/XI_19") (pintype "passive"))
      (node (ref "ZD2") (pin "2") (pinfunction "2_2") (pintype "passive"))
    )
    (net (code "23") (name "/SWCLK") (class "Default")
      (node (ref "CN1") (pin "3") (pinfunction "3_3") (pintype "passive"))
      (node (ref "U21") (pin "22") (pinfunction "M0/SWCLK/TX1/T1I/T1O/ADC11_22") (pintype "passive"))
    )
    (net (code "24") (name "/SWDIO") (class "Default")
      (node (ref "CN1") (pin "4") (pinfunction "4_4") (pintype "passive"))
      (node (ref "U21") (pin "23") (pinfunction "M1/SWDIO/UART1RX/BT3O_23") (pintype "passive"))
    )
    (net (code "25") (name "/U") (class "Default")
      (node (ref "C3") (pin "1") (pinfunction "1_1") (pintype "passive"))
      (node (ref "C96") (pin "2") (pinfunction "2_2") (pintype "passive"))
      (node (ref "J1") (pin "1") (pinfunction "1_1") (pintype "passive"))
      (node (ref "Q12") (pin "3") (pinfunction "D_3") (pintype "passive"))
      (node (ref "Q13") (pin "2") (pinfunction "S_2") (pintype "passive"))
      (node (ref "R51") (pin "1") (pinfunction "1_1") (pintype "passive"))
      (node (ref "T1") (pin "1") (pinfunction "1_1") (pintype "passive"))
      (node (ref "U21") (pin "9") (pinfunction "HS1_9") (pintype "passive"))
    )
    (net (code "26") (name "/U-H") (class "Default")
      (node (ref "D10") (pin "2") (pinfunction "K_2") (pintype "passive"))
      (node (ref "R65") (pin "1") (pinfunction "1_1") (pintype "passive"))
      (node (ref "U") (pin "1") (pinfunction "1_1") (pintype "passive"))
      (node (ref "U21") (pin "10") (pinfunction "HO1_10") (pintype "passive"))
    )
    (net (code "27") (name "/U-L") (class "Default")
      (node (ref "D5") (pin "2") (pinfunction "K_2") (pintype "passive"))
      (node (ref "R66") (pin "1") (pinfunction "1_1") (pintype "passive"))
      (node (ref "U21") (pin "13") (pinfunction "LO1_13") (pintype "passive"))
      (node (ref "UL") (pin "1") (pinfunction "1_1") (pintype "passive"))
    )
    (net (code "28") (name "/U1-RST") (class "Default")
      (node (ref "C17") (pin "1") (pinfunction "1_1") (pintype "passive"))
      (node (ref "R30") (pin "2") (pinfunction "2_2") (pintype "passive"))
      (node (ref "U21") (pin "17") (pinfunction "RSET_17") (pintype "passive"))
    )
    (net (code "29") (name "/V") (class "Default")
      (node (ref "C11") (pin "2") (pinfunction "2_2") (pintype "passive"))
      (node (ref "C54") (pin "1") (pinfunction "1_1") (pintype "passive"))
      (node (ref "J1") (pin "2") (pinfunction "2_2") (pintype "passive"))
      (node (ref "Q10") (pin "3") (pinfunction "D_3") (pintype "passive"))
      (node (ref "Q11") (pin "2") (pinfunction "S_2") (pintype "passive"))
      (node (ref "R21") (pin "1") (pinfunction "1_1") (pintype "passive"))
      (node (ref "T3") (pin "1") (pinfunction "1_1") (pintype "passive"))
      (node (ref "U21") (pin "6") (pinfunction "HS2_6") (pintype "passive"))
    )
    (net (code "30") (name "/V-H") (class "Default")
      (node (ref "D22") (pin "2") (pinfunction "K_2") (pintype "passive"))
      (node (ref "R63") (pin "1") (pinfunction "1_1") (pintype "passive"))
      (node (ref "U21") (pin "7") (pinfunction "HO2_7") (pintype "passive"))
      (node (ref "V") (pin "1") (pinfunction "1_1") (pintype "passive"))
    )
    (net (code "31") (name "/V-L") (class "Default")
      (node (ref "D23") (pin "2") (pinfunction "K_2") (pintype "passive"))
      (node (ref "R64") (pin "1") (pinfunction "1_1") (pintype "passive"))
      (node (ref "U21") (pin "40") (pinfunction "LO2_40") (pintype "passive"))
      (node (ref "VL") (pin "1") (pinfunction "1_1") (pintype "passive"))
    )
    (net (code "32") (name "/VSP") (class "Default")
      (node (ref "C39") (pin "1") (pinfunction "1_1") (pintype "passive"))
      (node (ref "R1") (pin "1") (pinfunction "1_1") (pintype "passive"))
      (node (ref "R14") (pin "1") (pinfunction "1_1") (pintype "passive"))
      (node (ref "U21") (pin "28") (pinfunction "B5/QEB/SDA0/HALL1/T1I/T1O/ADC7/CMPVP1_28") (pintype "passive"))
    )
    (net (code "33") (name "/VSP2") (class "Default")
      (node (ref "CN2") (pin "2") (pinfunction "2_2") (pintype "passive"))
      (node (ref "R35") (pin "1") (pinfunction "1_1") (pintype "passive"))
    )
    (net (code "34") (name "/W") (class "Default")
      (node (ref "C56") (pin "1") (pinfunction "1_1") (pintype "passive"))
      (node (ref "C8") (pin "2") (pinfunction "2_2") (pintype "passive"))
      (node (ref "J1") (pin "3") (pinfunction "3_3") (pintype "passive"))
      (node (ref "Q8") (pin "3") (pinfunction "D_3") (pintype "passive"))
      (node (ref "Q9") (pin "2") (pinfunction "S_2") (pintype "passive"))
      (node (ref "R10") (pin "1") (pinfunction "1_1") (pintype "passive"))
      (node (ref "T4") (pin "1") (pinfunction "1_1") (pintype "passive"))
      (node (ref "U21") (pin "3") (pinfunction "HS3_3") (pintype "passive"))
    )
    (net (code "35") (name "/W-H") (class "Default")
      (node (ref "D24") (pin "2") (pinfunction "K_2") (pintype "passive"))
      (node (ref "R58") (pin "1") (pinfunction "1_1") (pintype "passive"))
      (node (ref "U21") (pin "4") (pinfunction "HO3_4") (pintype "passive"))
      (node (ref "W1") (pin "1") (pinfunction "1_1") (pintype "passive"))
    )
    (net (code "36") (name "/W-L") (class "Default")
      (node (ref "D25") (pin "2") (pinfunction "K_2") (pintype "passive"))
      (node (ref "R59") (pin "1") (pinfunction "1_1") (pintype "passive"))
      (node (ref "U21") (pin "1") (pinfunction "LO3_1") (pintype "passive"))
      (node (ref "WL") (pin "1") (pinfunction "1_1") (pintype "passive"))
    )
    (net (code "37") (name "5V") (class "Default")
      (node (ref "C10") (pin "2") (pinfunction "2_2") (pintype "passive"))
      (node (ref "C15") (pin "2") (pinfunction "2_2") (pintype "passive"))
      (node (ref "C21") (pin "1") (pinfunction "1_1") (pintype "passive"))
      (node (ref "C22") (pin "2") (pinfunction "2_2") (pintype "passive"))
      (node (ref "C23") (pin "2") (pinfunction "2_2") (pintype "passive"))
      (node (ref "CN1") (pin "1") (pinfunction "1_1") (pintype "passive"))
      (node (ref "R137") (pin "2") (pinfunction "2_2") (pintype "passive"))
      (node (ref "R22") (pin "2") (pinfunction "2_2") (pintype "passive"))
      (node (ref "R29") (pin "2") (pinfunction "2_2") (pintype "passive"))
      (node (ref "R30") (pin "1") (pinfunction "1_1") (pintype "passive"))
      (node (ref "R33") (pin "1") (pinfunction "1_1") (pintype "passive"))
      (node (ref "U21") (pin "16") (pinfunction "VDD5V_16") (pintype "passive"))
      (node (ref "U21") (pin "21") (pinfunction "VDD5V-2_21") (pintype "passive"))
      (node (ref "U21") (pin "26") (pinfunction "VDD5V-3_26") (pintype "passive"))
      (node (ref "U3") (pin "1") (pinfunction "OUT_1") (pintype "passive"))
      (node (ref "VR1") (pin "1") (pinfunction "1_1") (pintype "passive"))
    )
    (net (code "38") (name "12V") (class "Default")
      (node (ref "C20") (pin "2") (pinfunction "2_2") (pintype "passive"))
      (node (ref "C38") (pin "1") (pinfunction "1_1") (pintype "passive"))
      (node (ref "C4") (pin "2") (pinfunction "2_2") (pintype "passive"))
      (node (ref "R23") (pin "1") (pinfunction "1_1") (pintype "passive"))
      (node (ref "R4") (pin "1") (pinfunction "1_1") (pintype "passive"))
      (node (ref "R5") (pin "1") (pinfunction "1_1") (pintype "passive"))
      (node (ref "R9") (pin "1") (pinfunction "1_1") (pintype "passive"))
      (node (ref "U2") (pin "1") (pinfunction "OUT_1") (pintype "passive"))
      (node (ref "U21") (pin "12") (pinfunction "VDD-12V_12") (pintype "passive"))
    )
    (net (code "39") (name "15V") (class "Default")
      (node (ref "C12") (pin "2") (pinfunction "2_2") (pintype "passive"))
      (node (ref "C13") (pin "1") (pinfunction "1_1") (pintype "passive"))
      (node (ref "C6") (pin "2") (pinfunction "2_2") (pintype "passive"))
      (node (ref "EC2") (pin "1") (pinfunction "1_1") (pintype "passive"))
      (node (ref "L2") (pin "1") (pinfunction "1_1") (pintype "passive"))
      (node (ref "R2") (pin "1") (pinfunction "1_1") (pintype "passive"))
      (node (ref "U2") (pin "3") (pinfunction "IN_3") (pintype "passive"))
    )
    (net (code "40") (name "A-GND") (class "Default")
      (node (ref "C12") (pin "1") (pinfunction "1_1") (pintype "passive"))
      (node (ref "C13") (pin "2") (pinfunction "2_2") (pintype "passive"))
      (node (ref "C16") (pin "2") (pinfunction "2_2") (pintype "passive"))
      (node (ref "C19") (pin "2") (pinfunction "2_2") (pintype "passive"))
      (node (ref "C20") (pin "1") (pinfunction "1_1") (pintype "passive"))
      (node (ref "C25") (pin "1") (pinfunction "1_1") (pintype "passive"))
      (node (ref "C29") (pin "2") (pinfunction "2_2") (pintype "passive"))
      (node (ref "C38") (pin "2") (pinfunction "2_2") (pintype "passive"))
      (node (ref "C4") (pin "1") (pinfunction "1_1") (pintype "passive"))
      (node (ref "C6") (pin "1") (pinfunction "1_1") (pintype "passive"))
      (node (ref "D2") (pin "2") (pinfunction "ANODE_2") (pintype "passive"))
      (node (ref "D8") (pin "2") (pinfunction "ANODE_2") (pintype "passive"))
      (node (ref "EC2") (pin "2") (pinfunction "2_2") (pintype "passive"))
      (node (ref "J6") (pin "2") (pinfunction "2_2") (pintype "passive"))
      (node (ref "R11") (pin "1") (pinfunction "1_1") (pintype "passive"))
      (node (ref "R17") (pin "1") (pinfunction "1_1") (pintype "passive"))
      (node (ref "R3") (pin "2") (pinfunction "2_2") (pintype "passive"))
      (node (ref "R6") (pin "2") (pinfunction "2_2") (pintype "passive"))
      (node (ref "RS1") (pin "1") (pinfunction "1_1") (pintype "passive"))
      (node (ref "U1") (pin "5") (pinfunction "VSS_5") (pintype "passive"))
      (node (ref "U1") (pin "6") (pinfunction "VSS_6") (pintype "passive"))
      (node (ref "U2") (pin "2") (pinfunction "GND_2") (pintype "passive"))
      (node (ref "U21") (pin "2") (pinfunction "PVSS_2") (pintype "passive"))
    )
    (net (code "41") (name "GND") (class "Default")
      (node (ref "C10") (pin "1") (pinfunction "1_1") (pintype "passive"))
      (node (ref "C14") (pin "2") (pinfunction "2_2") (pintype "passive"))
      (node (ref "C15") (pin "1") (pinfunction "1_1") (pintype "passive"))
      (node (ref "C17") (pin "2") (pinfunction "2_2") (pintype "passive"))
      (node (ref "C21") (pin "2") (pinfunction "2_2") (pintype "passive"))
      (node (ref "C22") (pin "1") (pinfunction "1_1") (pintype "passive"))
      (node (ref "C23") (pin "1") (pinfunction "1_1") (pintype "passive"))
      (node (ref "C5") (pin "1") (pinfunction "1_1") (pintype "passive"))
      (node (ref "C50") (pin "1") (pinfunction "1_1") (pintype "passive"))
      (node (ref "C65") (pin "2") (pinfunction "2_2") (pintype "passive"))
      (node (ref "C69") (pin "1") (pinfunction "1_1") (pintype "passive"))
      (node (ref "C7") (pin "1") (pinfunction "1_1") (pintype "passive"))
      (node (ref "C9") (pin "1") (pinfunction "1_1") (pintype "passive"))
      (node (ref "CN1") (pin "2") (pinfunction "2_2") (pintype "passive"))
      (node (ref "CN2") (pin "1") (pinfunction "1_1") (pintype "passive"))
      (node (ref "R11") (pin "2") (pinfunction "2_2") (pintype "passive"))
      (node (ref "R112") (pin "2") (pinfunction "2_2") (pintype "passive"))
      (node (ref "R34") (pin "2") (pinfunction "2_2") (pintype "passive"))
      (node (ref "R81") (pin "2") (pinfunction "2_2") (pintype "passive"))
      (node (ref "U21") (pin "14") (pinfunction "GND_14") (pintype "passive"))
      (node (ref "U21") (pin "41") (pinfunction "GND2_41") (pintype "passive"))
      (node (ref "U3") (pin "2") (pinfunction "GND_2") (pintype "passive"))
      (node (ref "ZD1") (pin "1") (pinfunction "1_1") (pintype "passive"))
      (node (ref "ZD2") (pin "1") (pinfunction "1_1") (pintype "passive"))
    )
    (net (code "42") (name "Net-(C2-Pad1)") (class "Default")
      (node (ref "C2") (pin "1") (pinfunction "1_1") (pintype "passive"))
      (node (ref "R25") (pin "1") (pinfunction "1_1") (pintype "passive"))
      (node (ref "R31") (pin "2") (pinfunction "2_2") (pintype "passive"))
    )
    (net (code "43") (name "Net-(C2-Pad2)") (class "Default")
      (node (ref "C2") (pin "2") (pinfunction "2_2") (pintype "passive"))
      (node (ref "R24") (pin "1") (pinfunction "1_1") (pintype "passive"))
      (node (ref "R32") (pin "2") (pinfunction "2_2") (pintype "passive"))
    )
    (net (code "44") (name "Net-(C7-Pad2)") (class "Default")
      (node (ref "C7") (pin "2") (pinfunction "2_2") (pintype "passive"))
      (node (ref "R12") (pin "1") (pinfunction "1_1") (pintype "passive"))
    )
    (net (code "45") (name "Net-(C18-Pad1)") (class "Default")
      (node (ref "C18") (pin "1") (pinfunction "1_1") (pintype "passive"))
      (node (ref "R16") (pin "1") (pinfunction "1_1") (pintype "passive"))
      (node (ref "R26") (pin "2") (pinfunction "2_2") (pintype "passive"))
    )
    (net (code "46") (name "Net-(C18-Pad2)") (class "Default")
      (node (ref "C18") (pin "2") (pinfunction "2_2") (pintype "passive"))
      (node (ref "R13") (pin "1") (pinfunction "1_1") (pintype "passive"))
      (node (ref "R27") (pin "2") (pinfunction "2_2") (pintype "passive"))
    )
    (net (code "47") (name "Net-(C39-Pad2)") (class "Default")
      (node (ref "C39") (pin "2") (pinfunction "2_2") (pintype "passive"))
      (node (ref "ESD5") (pin "2") (pinfunction "2_2") (pintype "passive"))
      (node (ref "R1") (pin "2") (pinfunction "2_2") (pintype "passive"))
      (node (ref "VR1") (pin "3") (pinfunction "3_3") (pintype "passive"))
    )
    (net (code "48") (name "Net-(C51-Pad1)") (class "Default")
      (node (ref "C51") (pin "1") (pinfunction "1_1") (pintype "passive"))
      (node (ref "R18") (pin "2") (pinfunction "2_2") (pintype "passive"))
      (node (ref "R49") (pin "1") (pinfunction "1_1") (pintype "passive"))
    )
    (net (code "49") (name "Net-(C51-Pad2)") (class "Default")
      (node (ref "C51") (pin "2") (pinfunction "2_2") (pintype "passive"))
      (node (ref "R17") (pin "2") (pinfunction "2_2") (pintype "passive"))
      (node (ref "R48") (pin "1") (pinfunction "1_1") (pintype "passive"))
    )
    (net (code "50") (name "Net-(D2-CATHODE)") (class "Default")
      (node (ref "D2") (pin "1") (pinfunction "CATHODE_1") (pintype "passive"))
      (node (ref "L2") (pin "2") (pinfunction "2_2") (pintype "passive"))
      (node (ref "U1") (pin "7") (pinfunction "SW_7") (pintype "passive"))
      (node (ref "U1") (pin "8") (pinfunction "SW_8") (pintype "passive"))
    )
    (net (code "51") (name "Net-(D4-A)") (class "Default")
      (node (ref "D4") (pin "1") (pinfunction "A_1") (pintype "passive"))
      (node (ref "R4") (pin "2") (pinfunction "2_2") (pintype "passive"))
    )
    (net (code "52") (name "Net-(D5-A)") (class "Default")
      (node (ref "C1") (pin "2") (pinfunction "2_2") (pintype "passive"))
      (node (ref "D5") (pin "1") (pinfunction "A_1") (pintype "passive"))
      (node (ref "Q13") (pin "1") (pinfunction "G_1") (pintype "passive"))
      (node (ref "R54") (pin "2") (pinfunction "2_2") (pintype "passive"))
      (node (ref "R66") (pin "2") (pinfunction "2_2") (pintype "passive"))
    )
    (net (code "53") (name "Net-(D7-A)") (class "Default")
      (node (ref "D7") (pin "1") (pinfunction "A_1") (pintype "passive"))
      (node (ref "R5") (pin "2") (pinfunction "2_2") (pintype "passive"))
    )
    (net (code "54") (name "Net-(D9-A)") (class "Default")
      (node (ref "D9") (pin "1") (pinfunction "A_1") (pintype "passive"))
      (node (ref "R23") (pin "2") (pinfunction "2_2") (pintype "passive"))
    )
    (net (code "55") (name "Net-(D10-A)") (class "Default")
      (node (ref "C3") (pin "2") (pinfunction "2_2") (pintype "passive"))
      (node (ref "D10") (pin "1") (pinfunction "A_1") (pintype "passive"))
      (node (ref "Q12") (pin "1") (pinfunction "G_1") (pintype "passive"))
      (node (ref "R51") (pin "2") (pinfunction "2_2") (pintype "passive"))
      (node (ref "R65") (pin "2") (pinfunction "2_2") (pintype "passive"))
    )
    (net (code "56") (name "Net-(D22-A)") (class "Default")
      (node (ref "C54") (pin "2") (pinfunction "2_2") (pintype "passive"))
      (node (ref "D22") (pin "1") (pinfunction "A_1") (pintype "passive"))
      (node (ref "Q10") (pin "1") (pinfunction "G_1") (pintype "passive"))
      (node (ref "R21") (pin "2") (pinfunction "2_2") (pintype "passive"))
      (node (ref "R63") (pin "2") (pinfunction "2_2") (pintype "passive"))
    )
    (net (code "57") (name "Net-(D23-A)") (class "Default")
      (node (ref "C55") (pin "2") (pinfunction "2_2") (pintype "passive"))
      (node (ref "D23") (pin "1") (pinfunction "A_1") (pintype "passive"))
      (node (ref "Q11") (pin "1") (pinfunction "G_1") (pintype "passive"))
      (node (ref "R43") (pin "2") (pinfunction "2_2") (pintype "passive"))
      (node (ref "R64") (pin "2") (pinfunction "2_2") (pintype "passive"))
    )
    (net (code "58") (name "Net-(D24-A)") (class "Default")
      (node (ref "C56") (pin "2") (pinfunction "2_2") (pintype "passive"))
      (node (ref "D24") (pin "1") (pinfunction "A_1") (pintype "passive"))
      (node (ref "Q8") (pin "1") (pinfunction "G_1") (pintype "passive"))
      (node (ref "R10") (pin "2") (pinfunction "2_2") (pintype "passive"))
      (node (ref "R58") (pin "2") (pinfunction "2_2") (pintype "passive"))
    )
    (net (code "59") (name "Net-(D25-A)") (class "Default")
      (node (ref "C57") (pin "2") (pinfunction "2_2") (pintype "passive"))
      (node (ref "D25") (pin "1") (pinfunction "A_1") (pintype "passive"))
      (node (ref "Q9") (pin "1") (pinfunction "G_1") (pintype "passive"))
      (node (ref "R59") (pin "2") (pinfunction "2_2") (pintype "passive"))
      (node (ref "R7") (pin "2") (pinfunction "2_2") (pintype "passive"))
    )
    (net (code "60") (name "Net-(ESD5-Pad1)") (class "Default")
      (node (ref "ESD5") (pin "1") (pinfunction "1_1") (pintype "passive"))
      (node (ref "R14") (pin "2") (pinfunction "2_2") (pintype "passive"))
      (node (ref "VR1") (pin "W") (pinfunction "W_W") (pintype "passive"))
    )
    (net (code "61") (name "Net-(R80-Pad1)") (class "Default")
      (node (ref "R80") (pin "1") (pinfunction "1_1") (pintype "passive"))
      (node (ref "R81") (pin "1") (pinfunction "1_1") (pintype "passive"))
      (node (ref "R82") (pin "2") (pinfunction "2_2") (pintype "passive"))
    )
    (net (code "62") (name "Net-(U1-EN)") (class "Default")
      (node (ref "R8") (pin "1") (pinfunction "1_1") (pintype "passive"))
      (node (ref "U1") (pin "2") (pinfunction "EN_2") (pintype "passive"))
    )
    (net (code "63") (name "Net-(U1-FB)") (class "Default")
      (node (ref "R2") (pin "2") (pinfunction "2_2") (pintype "passive"))
      (node (ref "R6") (pin "1") (pinfunction "1_1") (pintype "passive"))
      (node (ref "U1") (pin "4") (pinfunction "FB_4") (pintype "passive"))
    )
    (net (code "64") (name "Net-(U1-FS)") (class "Default")
      (node (ref "R3") (pin "1") (pinfunction "1_1") (pintype "passive"))
      (node (ref "U1") (pin "3") (pinfunction "FS_3") (pintype "passive"))
    )
    (net (code "65") (name "Net-(U3-IN)") (class "Default")
      (node (ref "C5") (pin "2") (pinfunction "2_2") (pintype "passive"))
      (node (ref "C9") (pin "2") (pinfunction "2_2") (pintype "passive"))
      (node (ref "R9") (pin "2") (pinfunction "2_2") (pintype "passive"))
      (node (ref "U3") (pin "3") (pinfunction "IN_3") (pintype "passive"))
    )
    (net (code "66") (name "Net-(U21-B10{slash}PWM0AN{slash}T0I{slash}T0O{slash}ISP)") (class "Default")
      (node (ref "R112") (pin "1") (pinfunction "1_1") (pintype "passive"))
      (node (ref "U21") (pin "18") (pinfunction "B10/PWM0AN/T0I/T0O/ISP_18") (pintype "passive"))
    )
    (net (code "67") (name "VDD") (class "Default")
      (node (ref "C16") (pin "1") (pinfunction "1_1") (pintype "passive"))
      (node (ref "C19") (pin "1") (pinfunction "1_1") (pintype "passive"))
      (node (ref "C25") (pin "2") (pinfunction "2_2") (pintype "passive"))
      (node (ref "C29") (pin "1") (pinfunction "1_1") (pintype "passive"))
      (node (ref "D8") (pin "1") (pinfunction "CATHODE_1") (pintype "passive"))
      (node (ref "J6") (pin "1") (pinfunction "1_1") (pintype "passive"))
      (node (ref "Q10") (pin "2") (pinfunction "S_2") (pintype "passive"))
      (node (ref "Q12") (pin "2") (pinfunction "S_2") (pintype "passive"))
      (node (ref "Q8") (pin "2") (pinfunction "S_2") (pintype "passive"))
      (node (ref "R8") (pin "2") (pinfunction "2_2") (pintype "passive"))
      (node (ref "R80") (pin "2") (pinfunction "2_2") (pintype "passive"))
      (node (ref "U1") (pin "1") (pinfunction "IN_1") (pintype "passive"))
    )
    (net (code "68") (name "unconnected-(CN2-Pad4)") (class "Default")
      (node (ref "CN2") (pin "4") (pinfunction "4_4") (pintype "passive"))
    )
    (net (code "69") (name "unconnected-(MARK1-Pad1)") (class "Default")
      (node (ref "MARK1") (pin "1") (pinfunction "1_1") (pintype "passive"))
    )
    (net (code "70") (name "unconnected-(MARK2-Pad1)") (class "Default")
      (node (ref "MARK2") (pin "1") (pinfunction "1_1") (pintype "passive"))
    )
    (net (code "71") (name "unconnected-(MARK3-Pad1)") (class "Default")
      (node (ref "MARK3") (pin "1") (pinfunction "1_1") (pintype "passive"))
    )
    (net (code "72") (name "unconnected-(MARK4-Pad1)") (class "Default")
      (node (ref "MARK4") (pin "1") (pinfunction "1_1") (pintype "passive"))
    )
    (net (code "73") (name "unconnected-(T2-Pad1)") (class "Default")
      (node (ref "T2") (pin "1") (pinfunction "1_1") (pintype "passive"))
    )
    (net (code "74") (name "unconnected-(T6-Pad1)") (class "Default")
      (node (ref "T6") (pin "1") (pinfunction "1_1") (pintype "passive"))
    )
    (net (code "75") (name "unconnected-(U21-M3{slash}SCL0{slash}TX0{slash}CAN0RX{slash}PWM{slash}HALL1-Pad24)") (class "Default")
      (node (ref "U21") (pin "24") (pinfunction "M3/SCL0/TX0/CAN0RX/PWM/HALL1_24") (pintype "passive"))
    )
    (net (code "76") (name "unconnected-(U21-M4{slash}SDA0{slash}RX0{slash}CAN0TX{slash}PWM{slash}HALL2-Pad25)") (class "Default")
      (node (ref "U21") (pin "25") (pinfunction "M4/SDA0/RX0/CAN0TX/PWM/HALL2_25") (pintype "passive"))
    )
  )
)
